# Celestron_Telescope_GPSRX-BT-WiFi-2_0.net
KiCad netlist of a schematic drawn in EAGLE
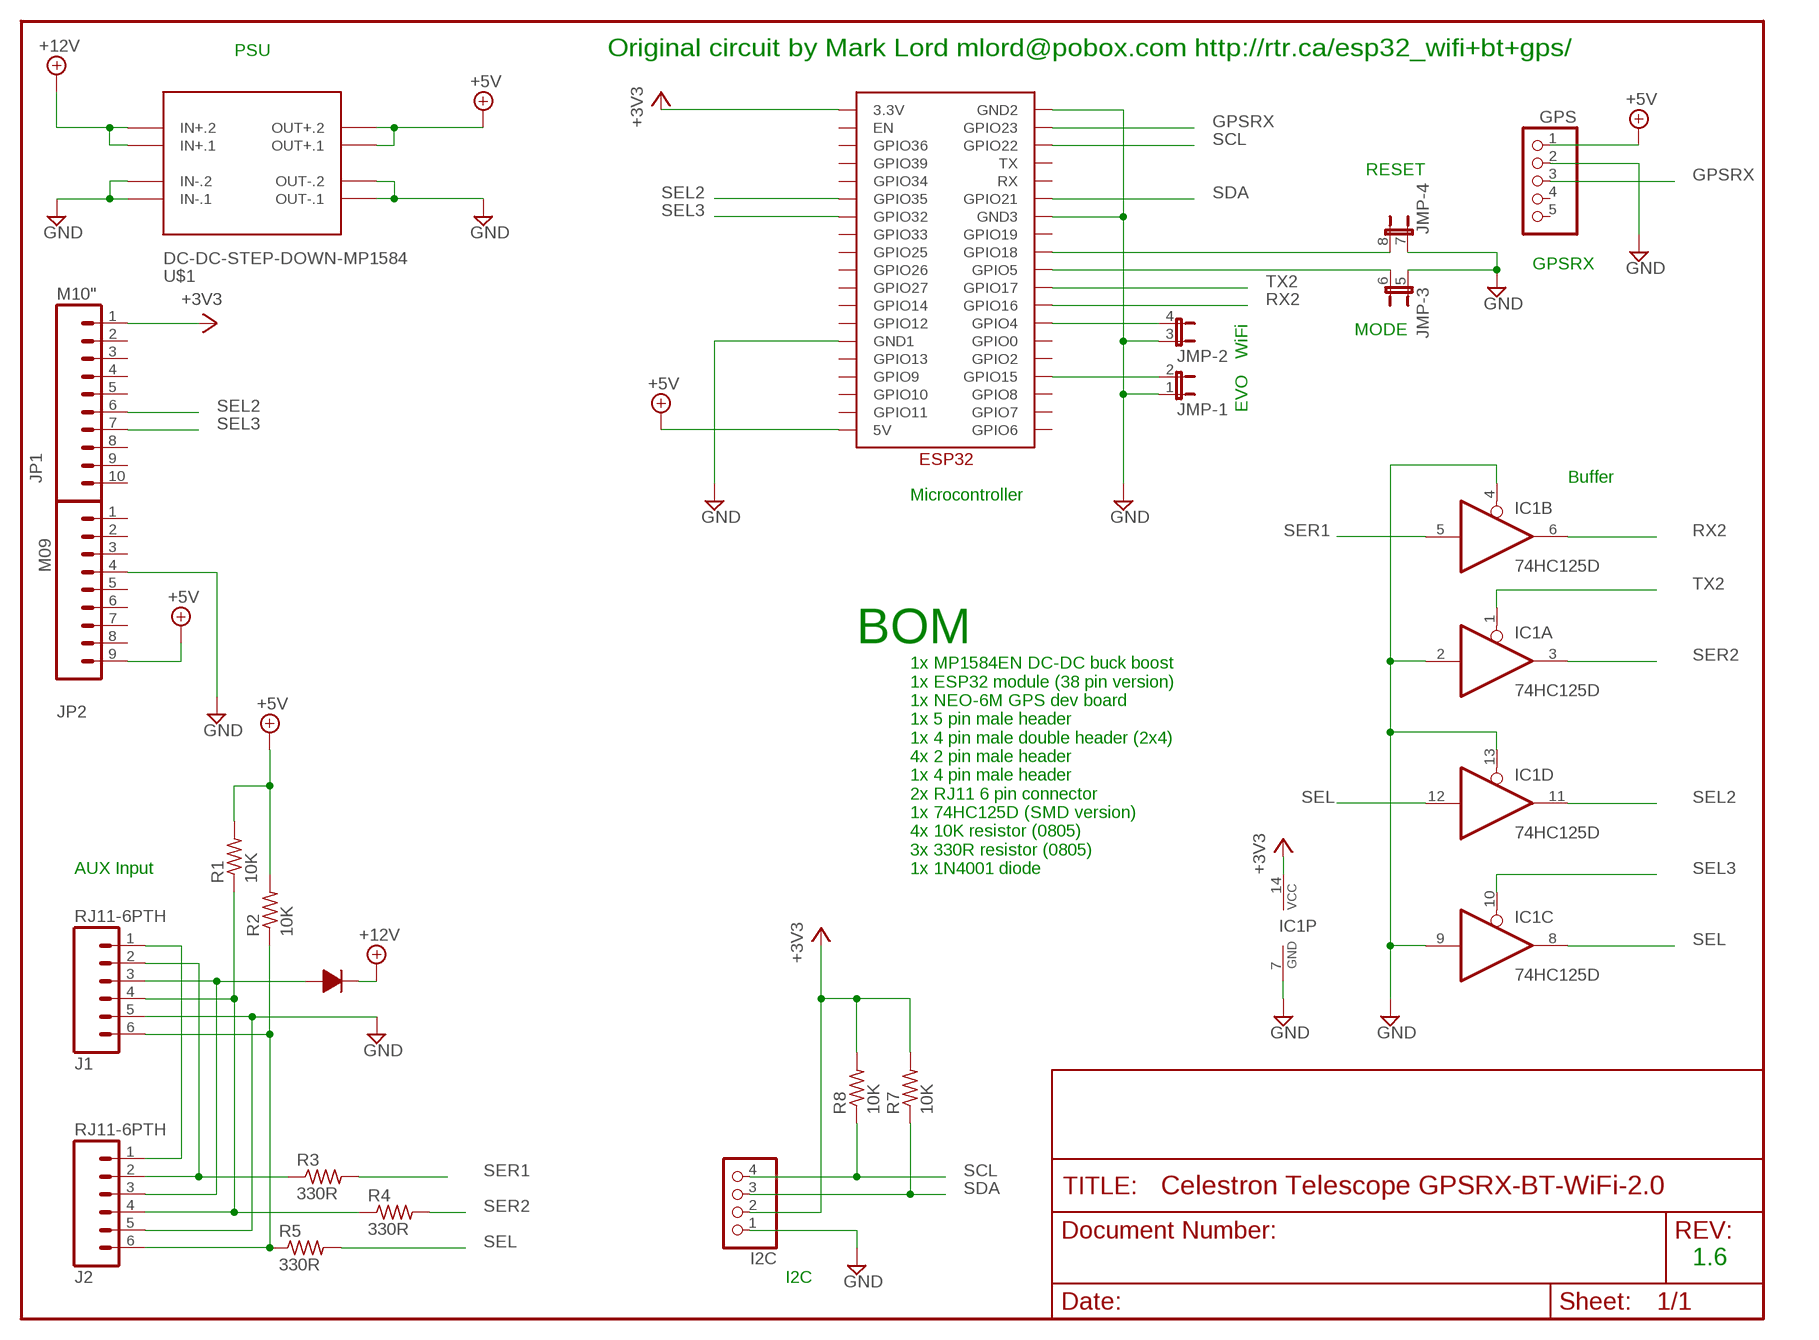
[diagram p0: schematic, sheet 1]

(export (version "E")
  (design (tool "Eeschema 10.0.6"))
  (components
    (comp (ref "GPS")
      (value "PINHD-1X5")
      (footprint "eagle-import:1X05")
      (libsource (lib "eagle-import") (part "PINHD-1X5"))
    )
    (comp (ref "I2C")
      (value "PINHD-1X4")
      (footprint "eagle-import:1X04")
      (libsource (lib "eagle-import") (part "PINHD-1X4"))
    )
    (comp (ref "IC1")
      (value "74HC125D")
      (footprint "eagle-import:SO14")
      (libsource (lib "eagle-import") (part "74125DHC"))
    )
    (comp (ref "J1")
      (value "RJ11-6PTH")
      (footprint "eagle-import:RJ11-6")
      (libsource (lib "eagle-import") (part "RJ11-6PTH"))
    )
    (comp (ref "J2")
      (value "RJ11-6PTH")
      (footprint "eagle-import:RJ11-6")
      (libsource (lib "eagle-import") (part "RJ11-6PTH"))
    )
    (comp (ref "JMP")
      (value "JP4QE")
      (footprint "eagle-import:JP4Q")
      (libsource (lib "eagle-import") (part "JP4QE"))
    )
    (comp (ref "JP1")
      (value "M10\"")
      (footprint "eagle-import:1X10")
      (libsource (lib "eagle-import") (part "M10{dblquote}"))
    )
    (comp (ref "JP2")
      (value "M09")
      (footprint "eagle-import:1X09")
      (libsource (lib "eagle-import") (part "M09"))
    )
    (comp (ref "R1")
      (value "10K")
      (footprint "eagle-import:M0805")
      (libsource (lib "eagle-import") (part "R-US_M0805"))
    )
    (comp (ref "R2")
      (value "10K")
      (footprint "eagle-import:M0805")
      (libsource (lib "eagle-import") (part "R-US_M0805"))
    )
    (comp (ref "R3")
      (value "330R")
      (footprint "eagle-import:M0805")
      (libsource (lib "eagle-import") (part "R-US_M0805"))
    )
    (comp (ref "R4")
      (value "330R")
      (footprint "eagle-import:M0805")
      (libsource (lib "eagle-import") (part "R-US_M0805"))
    )
    (comp (ref "R5")
      (value "330R")
      (footprint "eagle-import:M0805")
      (libsource (lib "eagle-import") (part "R-US_M0805"))
    )
    (comp (ref "R7")
      (value "10K")
      (footprint "eagle-import:M0805")
      (libsource (lib "eagle-import") (part "R-US_M0805"))
    )
    (comp (ref "R8")
      (value "10K")
      (footprint "eagle-import:M0805")
      (libsource (lib "eagle-import") (part "R-US_M0805"))
    )
    (comp (ref "U$1")
      (value "DC-DC-STEP-DOWN-MP1584")
      (footprint "eagle-import:DC-DC-STEP-DOWN-MP1584")
      (libsource (lib "eagle-import") (part "DC-DC-STEP-DOWN-MP1584"))
    )
    (comp (ref "U$2")
      (value "1N4001")
      (footprint "eagle-import:DIODE-12.70")
      (libsource (lib "eagle-import") (part "1N4001"))
    )
    (comp (ref "U$3")
      (value "ESP32")
      (footprint "eagle-import:ESP32")
      (libsource (lib "eagle-import") (part "ESP32"))
    )
  )
  (nets
    (net (code "1") (name "+3V3") (class "Default")
      (node (ref "I2C") (pin "2") (pinfunction "2_2") (pintype "passive"))
      (node (ref "IC1") (pin "14") (pinfunction "VCC_14") (pintype "power_in"))
      (node (ref "JP1") (pin "1") (pinfunction "1_1") (pintype "passive"))
      (node (ref "R7") (pin "2") (pinfunction "2_2") (pintype "passive"))
      (node (ref "R8") (pin "2") (pinfunction "2_2") (pintype "passive"))
      (node (ref "U$3") (pin "3.3V") (pinfunction "3.3V_3.3V") (pintype "bidirectional"))
    )
    (net (code "2") (name "+5V") (class "Default")
      (node (ref "GPS") (pin "1") (pinfunction "1_1") (pintype "passive"))
      (node (ref "JP2") (pin "9") (pinfunction "9_9") (pintype "passive"))
      (node (ref "R1") (pin "2") (pinfunction "2_2") (pintype "passive"))
      (node (ref "R2") (pin "2") (pinfunction "2_2") (pintype "passive"))
      (node (ref "U$1") (pin "OUT+.1") (pinfunction "OUT+.1_OUT+.1") (pintype "bidirectional"))
      (node (ref "U$1") (pin "OUT+.2") (pinfunction "OUT+.2_OUT+.2") (pintype "bidirectional"))
      (node (ref "U$3") (pin "5V") (pinfunction "5V_5V") (pintype "bidirectional"))
    )
    (net (code "3") (name "+12V") (class "Default")
      (node (ref "U$1") (pin "IN+.1") (pinfunction "IN+.1_IN+.1") (pintype "bidirectional"))
      (node (ref "U$1") (pin "IN+.2") (pinfunction "IN+.2_IN+.2") (pintype "bidirectional"))
      (node (ref "U$2") (pin "P$2") (pinfunction "P$2_P$2") (pintype "passive"))
    )
    (net (code "4") (name "/GPSRX") (class "Default")
      (node (ref "GPS") (pin "3") (pinfunction "3_3") (pintype "passive"))
      (node (ref "U$3") (pin "GPIO23") (pinfunction "GPIO23_GPIO23") (pintype "bidirectional"))
    )
    (net (code "5") (name "/RX2") (class "Default")
      (node (ref "IC1") (pin "6") (pinfunction "O_6") (pintype "tri_state"))
      (node (ref "U$3") (pin "GPIO16") (pinfunction "GPIO16_GPIO16") (pintype "bidirectional"))
    )
    (net (code "6") (name "/SCL") (class "Default")
      (node (ref "I2C") (pin "4") (pinfunction "4_4") (pintype "passive"))
      (node (ref "R8") (pin "1") (pinfunction "1_1") (pintype "passive"))
      (node (ref "U$3") (pin "GPIO22") (pinfunction "GPIO22_GPIO22") (pintype "bidirectional"))
    )
    (net (code "7") (name "/SDA") (class "Default")
      (node (ref "I2C") (pin "3") (pinfunction "3_3") (pintype "passive"))
      (node (ref "R7") (pin "1") (pinfunction "1_1") (pintype "passive"))
      (node (ref "U$3") (pin "GPIO21") (pinfunction "GPIO21_GPIO21") (pintype "bidirectional"))
    )
    (net (code "8") (name "/SEL") (class "Default")
      (node (ref "IC1") (pin "12") (pinfunction "I_12") (pintype "input"))
      (node (ref "IC1") (pin "8") (pinfunction "O_8") (pintype "tri_state"))
      (node (ref "R5") (pin "2") (pinfunction "2_2") (pintype "passive"))
    )
    (net (code "9") (name "/SEL2") (class "Default")
      (node (ref "IC1") (pin "11") (pinfunction "O_11") (pintype "tri_state"))
      (node (ref "JP1") (pin "6") (pinfunction "6_6") (pintype "passive"))
      (node (ref "U$3") (pin "GPIO35") (pinfunction "GPIO35_GPIO35") (pintype "bidirectional"))
    )
    (net (code "10") (name "/SEL3") (class "Default")
      (node (ref "IC1") (pin "10") (pinfunction "OE_10") (pintype "input"))
      (node (ref "JP1") (pin "7") (pinfunction "7_7") (pintype "passive"))
      (node (ref "U$3") (pin "GPIO32") (pinfunction "GPIO32_GPIO32") (pintype "bidirectional"))
    )
    (net (code "11") (name "/SER1") (class "Default")
      (node (ref "IC1") (pin "5") (pinfunction "I_5") (pintype "input"))
      (node (ref "R3") (pin "2") (pinfunction "2_2") (pintype "passive"))
    )
    (net (code "12") (name "/SER2") (class "Default")
      (node (ref "IC1") (pin "3") (pinfunction "O_3") (pintype "tri_state"))
      (node (ref "R4") (pin "2") (pinfunction "2_2") (pintype "passive"))
    )
    (net (code "13") (name "/TX2") (class "Default")
      (node (ref "IC1") (pin "1") (pinfunction "OE_1") (pintype "input"))
      (node (ref "U$3") (pin "GPIO17") (pinfunction "GPIO17_GPIO17") (pintype "bidirectional"))
    )
    (net (code "14") (name "GND") (class "Default")
      (node (ref "GPS") (pin "2") (pinfunction "2_2") (pintype "passive"))
      (node (ref "I2C") (pin "1") (pinfunction "1_1") (pintype "passive"))
      (node (ref "IC1") (pin "13") (pinfunction "OE_13") (pintype "input"))
      (node (ref "IC1") (pin "2") (pinfunction "I_2") (pintype "input"))
      (node (ref "IC1") (pin "4") (pinfunction "OE_4") (pintype "input"))
      (node (ref "IC1") (pin "7") (pinfunction "GND_7") (pintype "power_in"))
      (node (ref "IC1") (pin "9") (pinfunction "I_9") (pintype "input"))
      (node (ref "J1") (pin "5") (pinfunction "5_5") (pintype "passive"))
      (node (ref "J2") (pin "5") (pinfunction "5_5") (pintype "passive"))
      (node (ref "JMP") (pin "1") (pinfunction "1_1") (pintype "passive"))
      (node (ref "JMP") (pin "3") (pinfunction "1_3") (pintype "passive"))
      (node (ref "JMP") (pin "5") (pinfunction "1_5") (pintype "passive"))
      (node (ref "JMP") (pin "7") (pinfunction "1_7") (pintype "passive"))
      (node (ref "JP2") (pin "4") (pinfunction "4_4") (pintype "passive"))
      (node (ref "U$1") (pin "IN-.1") (pinfunction "IN-.1_IN-.1") (pintype "bidirectional"))
      (node (ref "U$1") (pin "IN-.2") (pinfunction "IN-.2_IN-.2") (pintype "bidirectional"))
      (node (ref "U$1") (pin "OUT-.1") (pinfunction "OUT-.1_OUT-.1") (pintype "bidirectional"))
      (node (ref "U$1") (pin "OUT-.2") (pinfunction "OUT-.2_OUT-.2") (pintype "bidirectional"))
      (node (ref "U$3") (pin "GND1") (pinfunction "GND1_GND1") (pintype "bidirectional"))
      (node (ref "U$3") (pin "GND2") (pinfunction "GND2_GND2") (pintype "bidirectional"))
      (node (ref "U$3") (pin "GND3") (pinfunction "GND3_GND3") (pintype "bidirectional"))
    )
    (net (code "15") (name "Net-(J1-Pad1)") (class "Default")
      (node (ref "J1") (pin "1") (pinfunction "1_1") (pintype "passive"))
      (node (ref "J2") (pin "1") (pinfunction "1_1") (pintype "passive"))
    )
    (net (code "16") (name "Net-(J1-Pad2)") (class "Default")
      (node (ref "J1") (pin "2") (pinfunction "2_2") (pintype "passive"))
      (node (ref "J2") (pin "2") (pinfunction "2_2") (pintype "passive"))
      (node (ref "R3") (pin "1") (pinfunction "1_1") (pintype "passive"))
    )
    (net (code "17") (name "Net-(J1-Pad3)") (class "Default")
      (node (ref "J1") (pin "3") (pinfunction "3_3") (pintype "passive"))
      (node (ref "J2") (pin "3") (pinfunction "3_3") (pintype "passive"))
      (node (ref "U$2") (pin "P$1") (pinfunction "P$1_P$1") (pintype "passive"))
    )
    (net (code "18") (name "Net-(J1-Pad4)") (class "Default")
      (node (ref "J1") (pin "4") (pinfunction "4_4") (pintype "passive"))
      (node (ref "J2") (pin "4") (pinfunction "4_4") (pintype "passive"))
      (node (ref "R1") (pin "1") (pinfunction "1_1") (pintype "passive"))
      (node (ref "R4") (pin "1") (pinfunction "1_1") (pintype "passive"))
    )
    (net (code "19") (name "Net-(J1-Pad6)") (class "Default")
      (node (ref "J1") (pin "6") (pinfunction "6_6") (pintype "passive"))
      (node (ref "J2") (pin "6") (pinfunction "6_6") (pintype "passive"))
      (node (ref "R2") (pin "1") (pinfunction "1_1") (pintype "passive"))
      (node (ref "R5") (pin "1") (pinfunction "1_1") (pintype "passive"))
    )
    (net (code "20") (name "Net-(JMP-Pad2)") (class "Default")
      (node (ref "JMP") (pin "2") (pinfunction "2_2") (pintype "passive"))
      (node (ref "U$3") (pin "GPIO15") (pinfunction "GPIO15_GPIO15") (pintype "bidirectional"))
    )
    (net (code "21") (name "Net-(JMPB-2)") (class "Default")
      (node (ref "JMP") (pin "4") (pinfunction "2_4") (pintype "passive"))
      (node (ref "U$3") (pin "GPIO4") (pinfunction "GPIO4_GPIO4") (pintype "bidirectional"))
    )
    (net (code "22") (name "Net-(JMPC-2)") (class "Default")
      (node (ref "JMP") (pin "6") (pinfunction "2_6") (pintype "passive"))
      (node (ref "U$3") (pin "GPIO5") (pinfunction "GPIO5_GPIO5") (pintype "bidirectional"))
    )
    (net (code "23") (name "Net-(JMPD-2)") (class "Default")
      (node (ref "JMP") (pin "8") (pinfunction "2_8") (pintype "passive"))
      (node (ref "U$3") (pin "GPIO18") (pinfunction "GPIO18_GPIO18") (pintype "bidirectional"))
    )
    (net (code "24") (name "unconnected-(GPS-Pad4)") (class "Default")
      (node (ref "GPS") (pin "4") (pinfunction "4_4") (pintype "passive"))
    )
    (net (code "25") (name "unconnected-(GPS-Pad5)") (class "Default")
      (node (ref "GPS") (pin "5") (pinfunction "5_5") (pintype "passive"))
    )
    (net (code "26") (name "unconnected-(JP1-Pad2)") (class "Default")
      (node (ref "JP1") (pin "2") (pinfunction "2_2") (pintype "passive"))
    )
    (net (code "27") (name "unconnected-(JP1-Pad3)") (class "Default")
      (node (ref "JP1") (pin "3") (pinfunction "3_3") (pintype "passive"))
    )
    (net (code "28") (name "unconnected-(JP1-Pad4)") (class "Default")
      (node (ref "JP1") (pin "4") (pinfunction "4_4") (pintype "passive"))
    )
    (net (code "29") (name "unconnected-(JP1-Pad5)") (class "Default")
      (node (ref "JP1") (pin "5") (pinfunction "5_5") (pintype "passive"))
    )
    (net (code "30") (name "unconnected-(JP1-Pad8)") (class "Default")
      (node (ref "JP1") (pin "8") (pinfunction "8_8") (pintype "passive"))
    )
    (net (code "31") (name "unconnected-(JP1-Pad9)") (class "Default")
      (node (ref "JP1") (pin "9") (pinfunction "9_9") (pintype "passive"))
    )
    (net (code "32") (name "unconnected-(JP1-Pad10)") (class "Default")
      (node (ref "JP1") (pin "10") (pinfunction "10_10") (pintype "passive"))
    )
    (net (code "33") (name "unconnected-(JP2-Pad1)") (class "Default")
      (node (ref "JP2") (pin "1") (pinfunction "1_1") (pintype "passive"))
    )
    (net (code "34") (name "unconnected-(JP2-Pad2)") (class "Default")
      (node (ref "JP2") (pin "2") (pinfunction "2_2") (pintype "passive"))
    )
    (net (code "35") (name "unconnected-(JP2-Pad3)") (class "Default")
      (node (ref "JP2") (pin "3") (pinfunction "3_3") (pintype "passive"))
    )
    (net (code "36") (name "unconnected-(JP2-Pad5)") (class "Default")
      (node (ref "JP2") (pin "5") (pinfunction "5_5") (pintype "passive"))
    )
    (net (code "37") (name "unconnected-(JP2-Pad6)") (class "Default")
      (node (ref "JP2") (pin "6") (pinfunction "6_6") (pintype "passive"))
    )
    (net (code "38") (name "unconnected-(JP2-Pad7)") (class "Default")
      (node (ref "JP2") (pin "7") (pinfunction "7_7") (pintype "passive"))
    )
    (net (code "39") (name "unconnected-(JP2-Pad8)") (class "Default")
      (node (ref "JP2") (pin "8") (pinfunction "8_8") (pintype "passive"))
    )
    (net (code "40") (name "unconnected-(U$3-PadEN)") (class "Default")
      (node (ref "U$3") (pin "EN") (pinfunction "EN_EN") (pintype "bidirectional"))
    )
    (net (code "41") (name "unconnected-(U$3-PadGPIO0)") (class "Default")
      (node (ref "U$3") (pin "GPIO0") (pinfunction "GPIO0_GPIO0") (pintype "bidirectional"))
    )
    (net (code "42") (name "unconnected-(U$3-PadGPIO2)") (class "Default")
      (node (ref "U$3") (pin "GPIO2") (pinfunction "GPIO2_GPIO2") (pintype "bidirectional"))
    )
    (net (code "43") (name "unconnected-(U$3-PadGPIO6)") (class "Default")
      (node (ref "U$3") (pin "GPIO6") (pinfunction "GPIO6_GPIO6") (pintype "bidirectional"))
    )
    (net (code "44") (name "unconnected-(U$3-PadGPIO7)") (class "Default")
      (node (ref "U$3") (pin "GPIO7") (pinfunction "GPIO7_GPIO7") (pintype "bidirectional"))
    )
    (net (code "45") (name "unconnected-(U$3-PadGPIO8)") (class "Default")
      (node (ref "U$3") (pin "GPIO8") (pinfunction "GPIO8_GPIO8") (pintype "bidirectional"))
    )
    (net (code "46") (name "unconnected-(U$3-PadGPIO9)") (class "Default")
      (node (ref "U$3") (pin "GPIO9") (pinfunction "GPIO9_GPIO9") (pintype "bidirectional"))
    )
    (net (code "47") (name "unconnected-(U$3-PadGPIO10)") (class "Default")
      (node (ref "U$3") (pin "GPIO10") (pinfunction "GPIO10_GPIO10") (pintype "bidirectional"))
    )
    (net (code "48") (name "unconnected-(U$3-PadGPIO11)") (class "Default")
      (node (ref "U$3") (pin "GPIO11") (pinfunction "GPIO11_GPIO11") (pintype "bidirectional"))
    )
    (net (code "49") (name "unconnected-(U$3-PadGPIO12)") (class "Default")
      (node (ref "U$3") (pin "GPIO12") (pinfunction "GPIO12_GPIO12") (pintype "bidirectional"))
    )
    (net (code "50") (name "unconnected-(U$3-PadGPIO13)") (class "Default")
      (node (ref "U$3") (pin "GPIO13") (pinfunction "GPIO13_GPIO13") (pintype "bidirectional"))
    )
    (net (code "51") (name "unconnected-(U$3-PadGPIO14)") (class "Default")
      (node (ref "U$3") (pin "GPIO14") (pinfunction "GPIO14_GPIO14") (pintype "bidirectional"))
    )
    (net (code "52") (name "unconnected-(U$3-PadGPIO19)") (class "Default")
      (node (ref "U$3") (pin "GPIO19") (pinfunction "GPIO19_GPIO19") (pintype "bidirectional"))
    )
    (net (code "53") (name "unconnected-(U$3-PadGPIO25)") (class "Default")
      (node (ref "U$3") (pin "GPIO25") (pinfunction "GPIO25_GPIO25") (pintype "bidirectional"))
    )
    (net (code "54") (name "unconnected-(U$3-PadGPIO26)") (class "Default")
      (node (ref "U$3") (pin "GPIO26") (pinfunction "GPIO26_GPIO26") (pintype "bidirectional"))
    )
    (net (code "55") (name "unconnected-(U$3-PadGPIO27)") (class "Default")
      (node (ref "U$3") (pin "GPIO27") (pinfunction "GPIO27_GPIO27") (pintype "bidirectional"))
    )
    (net (code "56") (name "unconnected-(U$3-PadGPIO33)") (class "Default")
      (node (ref "U$3") (pin "GPIO33") (pinfunction "GPIO33_GPIO33") (pintype "bidirectional"))
    )
    (net (code "57") (name "unconnected-(U$3-PadGPIO34)") (class "Default")
      (node (ref "U$3") (pin "GPIO34") (pinfunction "GPIO34_GPIO34") (pintype "bidirectional"))
    )
    (net (code "58") (name "unconnected-(U$3-PadGPIO36)") (class "Default")
      (node (ref "U$3") (pin "GPIO36") (pinfunction "GPIO36_GPIO36") (pintype "bidirectional"))
    )
    (net (code "59") (name "unconnected-(U$3-PadGPIO39)") (class "Default")
      (node (ref "U$3") (pin "GPIO39") (pinfunction "GPIO39_GPIO39") (pintype "bidirectional"))
    )
    (net (code "60") (name "unconnected-(U$3-PadRX)") (class "Default")
      (node (ref "U$3") (pin "RX") (pinfunction "RX_RX") (pintype "bidirectional"))
    )
    (net (code "61") (name "unconnected-(U$3-PadTX)") (class "Default")
      (node (ref "U$3") (pin "TX") (pinfunction "TX_TX") (pintype "bidirectional"))
    )
  )
)
